# Rotary-Encoder.net
KiCad netlist of a schematic drawn in Altium Designer
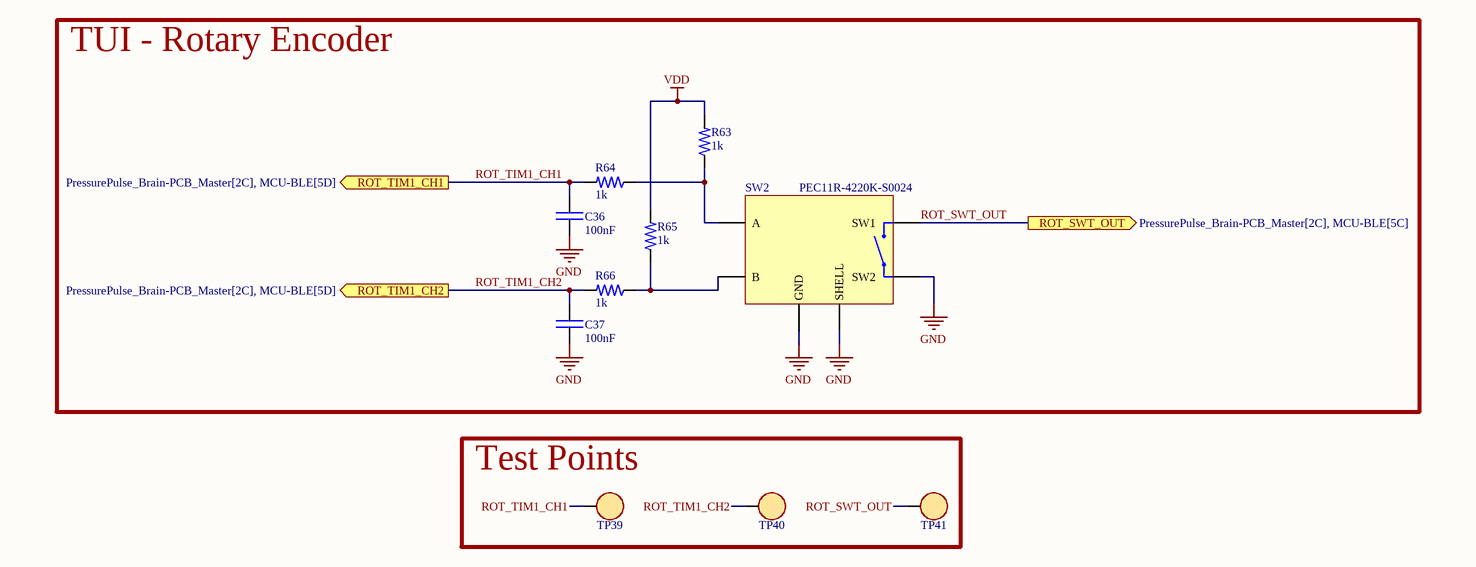
[diagram p0: Rotary-Encoder.SchDoc]

(export (version "E")
  (design (tool "Eeschema 10.0.6"))
  (components
    (comp (ref "C36")
      (value "100nF")
      (footprint "PressurePulse:0402C")
      (description "Capacitor")
      (fields (field (name "Comment") "CAP"))
      (libsource (lib "PressurePulse") (part "CAP"))
    )
    (comp (ref "C37")
      (value "100nF")
      (footprint "PressurePulse:0402C")
      (description "Capacitor")
      (fields (field (name "Comment") "CAP"))
      (libsource (lib "PressurePulse") (part "CAP"))
    )
    (comp (ref "R63")
      (value "1k")
      (footprint "PressurePulse:0402R")
      (description "Resistor")
      (fields (field (name "Comment") "RES"))
      (libsource (lib "PressurePulse") (part "RES"))
    )
    (comp (ref "R64")
      (value "1k")
      (footprint "PressurePulse:0402R")
      (description "Resistor")
      (fields (field (name "Comment") "RES"))
      (libsource (lib "PressurePulse") (part "RES"))
    )
    (comp (ref "R65")
      (value "1k")
      (footprint "PressurePulse:0402R")
      (description "Resistor")
      (fields (field (name "Comment") "RES"))
      (libsource (lib "PressurePulse") (part "RES"))
    )
    (comp (ref "R66")
      (value "1k")
      (footprint "PressurePulse:0402R")
      (description "Resistor")
      (fields (field (name "Comment") "RES"))
      (libsource (lib "PressurePulse") (part "RES"))
    )
    (comp (ref "SW2")
      (value "PEC11R-4220K-S0024")
      (footprint "PressurePulse:PEC11R-4220K-S0024")
      (description "Rotary Encoder Incremental 24 Quadrature, 2-Bit Vertical")
      (fields (field (name "MFR") "Bourns Inc."))
      (libsource (lib "PressurePulse") (part "ROT ENCODER W SWITCH"))
    )
    (comp (ref "TP39")
      (value "RH-5019")
      (footprint "PressurePulse:TP - RH-5019")
      (fields (field (name "MFR") "ronghe"))
      (libsource (lib "PressurePulse") (part "TEST POINT"))
    )
    (comp (ref "TP40")
      (value "RH-5019")
      (footprint "PressurePulse:TP - RH-5019")
      (fields (field (name "MFR") "ronghe"))
      (libsource (lib "PressurePulse") (part "TEST POINT"))
    )
    (comp (ref "TP41")
      (value "RH-5019")
      (footprint "PressurePulse:TP - RH-5019")
      (fields (field (name "MFR") "ronghe"))
      (libsource (lib "PressurePulse") (part "TEST POINT"))
    )
  )
  (nets
    (net (code "1") (name "/ROT_SWT_OUT") (class "Default")
      (node (ref "SW2") (pin "SW1") (pinfunction "SW1_SW1") (pintype "passive"))
      (node (ref "TP41") (pin "1") (pinfunction "1_1") (pintype "passive"))
    )
    (net (code "2") (name "/ROT_TIM1_CH1") (class "Default")
      (node (ref "C36") (pin "2") (pinfunction "2_2") (pintype "passive"))
      (node (ref "R64") (pin "2") (pinfunction "2_2") (pintype "passive"))
      (node (ref "TP39") (pin "1") (pinfunction "1_1") (pintype "passive"))
    )
    (net (code "3") (name "/ROT_TIM1_CH2") (class "Default")
      (node (ref "C37") (pin "2") (pinfunction "2_2") (pintype "passive"))
      (node (ref "R66") (pin "2") (pinfunction "2_2") (pintype "passive"))
      (node (ref "TP40") (pin "1") (pinfunction "1_1") (pintype "passive"))
    )
    (net (code "4") (name "GND") (class "Default")
      (node (ref "C36") (pin "1") (pinfunction "1_1") (pintype "passive"))
      (node (ref "C37") (pin "1") (pinfunction "1_1") (pintype "passive"))
      (node (ref "SW2") (pin "GND") (pinfunction "GND_GND") (pintype "passive"))
      (node (ref "SW2") (pin "SHELL") (pinfunction "SHELL_SHELL") (pintype "passive"))
      (node (ref "SW2") (pin "SW2") (pinfunction "SW2_SW2") (pintype "passive"))
    )
    (net (code "5") (name "Net-(R63-Pad1)") (class "Default")
      (node (ref "R63") (pin "1") (pinfunction "1_1") (pintype "passive"))
      (node (ref "R64") (pin "1") (pinfunction "1_1") (pintype "passive"))
      (node (ref "SW2") (pin "A") (pinfunction "A_A") (pintype "passive"))
    )
    (net (code "6") (name "Net-(R65-Pad1)") (class "Default")
      (node (ref "R65") (pin "1") (pinfunction "1_1") (pintype "passive"))
      (node (ref "R66") (pin "1") (pinfunction "1_1") (pintype "passive"))
      (node (ref "SW2") (pin "B") (pinfunction "B_B") (pintype "passive"))
    )
    (net (code "7") (name "VDD") (class "Default")
      (node (ref "R63") (pin "2") (pinfunction "2_2") (pintype "passive"))
      (node (ref "R65") (pin "2") (pinfunction "2_2") (pintype "passive"))
    )
  )
)
